# Tracksoar_SD_shield.net
KiCad netlist of a schematic drawn in EAGLE
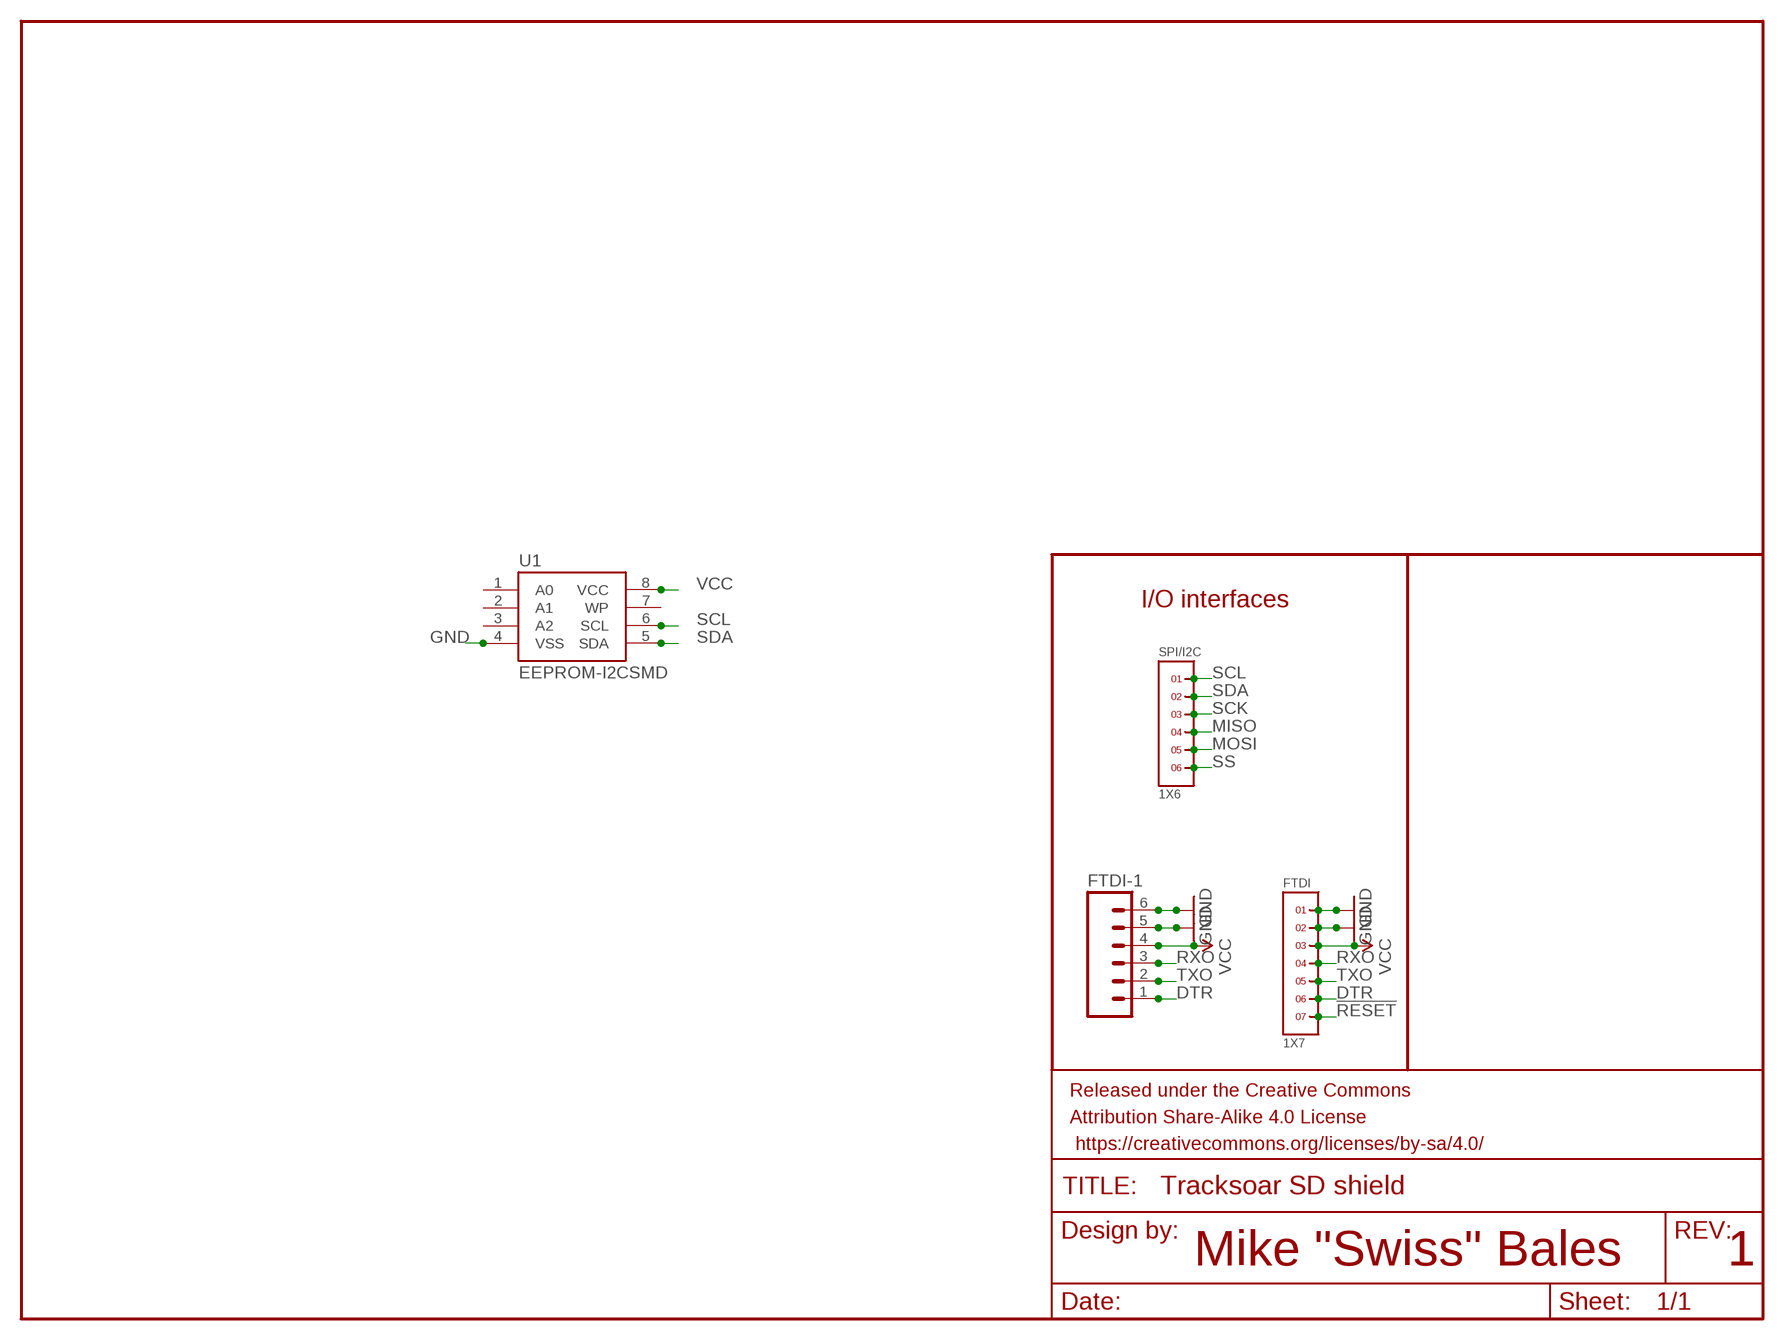
[diagram p0: schematic, sheet 1]

(export (version "E")
  (design (tool "Eeschema 10.0.6"))
  (components
    (comp (ref "FRAME1")
      (value "FRAME-LETTER")
      (footprint "eagle-import:CREATIVE_COMMONS")
      (libsource (lib "eagle-import") (part "FRAME-LETTER"))
    )
    (comp (ref "FTDI")
      (value "1X7")
      (footprint "eagle-import:1X7")
      (libsource (lib "eagle-import") (part "1X7"))
    )
    (comp (ref "FTDI-1")
      (value "M06LOCK_LONGPADS")
      (footprint "eagle-import:1X06_LOCK_LONGPADS")
      (libsource (lib "eagle-import") (part "M06LOCK_LONGPADS"))
    )
    (comp (ref "SPI/I2C")
      (value "1X6")
      (footprint "eagle-import:1X6")
      (libsource (lib "eagle-import") (part "1X6"))
    )
    (comp (ref "U1")
      (value "EEPROM-I2CSMD")
      (footprint "eagle-import:SO08")
      (libsource (lib "eagle-import") (part "EEPROM-I2CSMD"))
    )
  )
  (nets
    (net (code "1") (name "/DTR") (class "Default")
      (node (ref "FTDI") (pin "6") (pinfunction "6_6") (pintype "bidirectional"))
      (node (ref "FTDI-1") (pin "1") (pinfunction "1_1") (pintype "passive"))
    )
    (net (code "2") (name "/MISO") (class "Default")
      (node (ref "SPI/I2C") (pin "4") (pinfunction "4_4") (pintype "bidirectional"))
    )
    (net (code "3") (name "/MOSI") (class "Default")
      (node (ref "SPI/I2C") (pin "5") (pinfunction "5_5") (pintype "bidirectional"))
    )
    (net (code "4") (name "/RXO") (class "Default")
      (node (ref "FTDI") (pin "4") (pinfunction "4_4") (pintype "bidirectional"))
      (node (ref "FTDI-1") (pin "3") (pinfunction "3_3") (pintype "passive"))
    )
    (net (code "5") (name "/SCK") (class "Default")
      (node (ref "SPI/I2C") (pin "3") (pinfunction "3_3") (pintype "bidirectional"))
    )
    (net (code "6") (name "/SCL") (class "Default")
      (node (ref "SPI/I2C") (pin "1") (pinfunction "1_1") (pintype "bidirectional"))
      (node (ref "U1") (pin "6") (pinfunction "SCL_6") (pintype "bidirectional"))
    )
    (net (code "7") (name "/SDA") (class "Default")
      (node (ref "SPI/I2C") (pin "2") (pinfunction "2_2") (pintype "bidirectional"))
      (node (ref "U1") (pin "5") (pinfunction "SDA_5") (pintype "bidirectional"))
    )
    (net (code "8") (name "/SS") (class "Default")
      (node (ref "SPI/I2C") (pin "6") (pinfunction "6_6") (pintype "bidirectional"))
    )
    (net (code "9") (name "/TXO") (class "Default")
      (node (ref "FTDI") (pin "5") (pinfunction "5_5") (pintype "bidirectional"))
      (node (ref "FTDI-1") (pin "2") (pinfunction "2_2") (pintype "passive"))
    )
    (net (code "10") (name "/~{RESET}") (class "Default")
      (node (ref "FTDI") (pin "7") (pinfunction "7_7") (pintype "bidirectional"))
    )
    (net (code "11") (name "GND") (class "Default")
      (node (ref "FTDI") (pin "1") (pinfunction "1_1") (pintype "bidirectional"))
      (node (ref "FTDI") (pin "2") (pinfunction "2_2") (pintype "bidirectional"))
      (node (ref "FTDI-1") (pin "5") (pinfunction "5_5") (pintype "passive"))
      (node (ref "FTDI-1") (pin "6") (pinfunction "6_6") (pintype "passive"))
      (node (ref "U1") (pin "4") (pinfunction "VSS_4") (pintype "power_in"))
    )
    (net (code "12") (name "VCC") (class "Default")
      (node (ref "FTDI") (pin "3") (pinfunction "3_3") (pintype "bidirectional"))
      (node (ref "FTDI-1") (pin "4") (pinfunction "4_4") (pintype "passive"))
      (node (ref "U1") (pin "8") (pinfunction "VCC_8") (pintype "power_in"))
    )
    (net (code "13") (name "unconnected-(U1-A0-Pad1)") (class "Default")
      (node (ref "U1") (pin "1") (pinfunction "A0_1") (pintype "bidirectional"))
    )
    (net (code "14") (name "unconnected-(U1-A1-Pad2)") (class "Default")
      (node (ref "U1") (pin "2") (pinfunction "A1_2") (pintype "bidirectional"))
    )
    (net (code "15") (name "unconnected-(U1-A2-Pad3)") (class "Default")
      (node (ref "U1") (pin "3") (pinfunction "A2_3") (pintype "bidirectional"))
    )
    (net (code "16") (name "unconnected-(U1-WP-Pad7)") (class "Default")
      (node (ref "U1") (pin "7") (pinfunction "WP_7") (pintype "bidirectional"))
    )
  )
)
